# tas5753.net
KiCad netlist of a schematic drawn in EAGLE
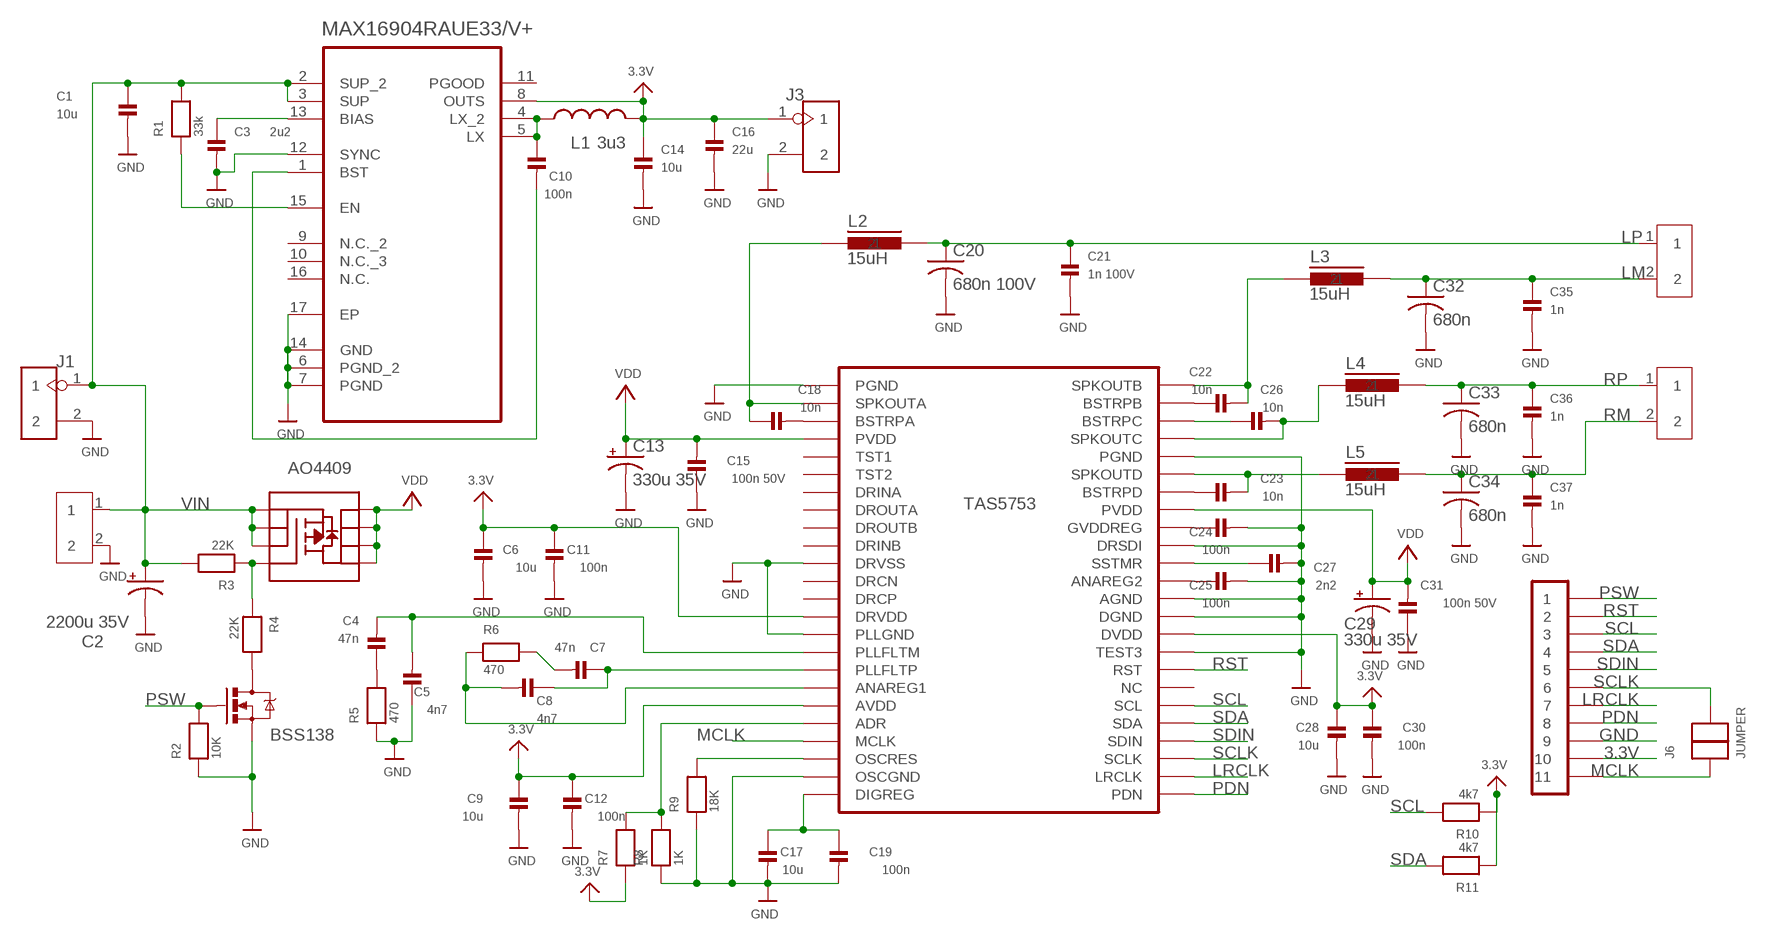
[diagram p0: schematic, sheet 1]

(export (version "E")
  (design (tool "Eeschema 10.0.6"))
  (components
    (comp (ref "C1")
      (value "10u")
      (footprint "eagle-import:0805")
      (libsource (lib "eagle-import") (part "CAP_CERAMIC0805"))
    )
    (comp (ref "C2")
      (value "2200u 35V")
      (footprint "eagle-import:CPOL-RADIAL-1000UF-25V")
      (libsource (lib "eagle-import") (part "CAP_POLPTH4"))
    )
    (comp (ref "C3")
      (value "2u2")
      (footprint "eagle-import:0805")
      (libsource (lib "eagle-import") (part "CAP_CERAMIC0805"))
    )
    (comp (ref "C4")
      (value "47n")
      (footprint "eagle-import:0603")
      (libsource (lib "eagle-import") (part "CAP_CERAMIC0603"))
    )
    (comp (ref "C5")
      (value "4n7")
      (footprint "eagle-import:0603")
      (libsource (lib "eagle-import") (part "CAP_CERAMIC0603"))
    )
    (comp (ref "C6")
      (value "10u")
      (footprint "eagle-import:0603")
      (libsource (lib "eagle-import") (part "CAP_CERAMIC0603"))
    )
    (comp (ref "C7")
      (value "47n")
      (footprint "eagle-import:0603")
      (libsource (lib "eagle-import") (part "CAP_CERAMIC0603"))
    )
    (comp (ref "C8")
      (value "4n7")
      (footprint "eagle-import:0603")
      (libsource (lib "eagle-import") (part "CAP_CERAMIC0603"))
    )
    (comp (ref "C9")
      (value "10u")
      (footprint "eagle-import:0603")
      (libsource (lib "eagle-import") (part "CAP_CERAMIC0603"))
    )
    (comp (ref "C10")
      (value "100n")
      (footprint "eagle-import:0603")
      (libsource (lib "eagle-import") (part "CAP_CERAMIC0603"))
    )
    (comp (ref "C11")
      (value "100n")
      (footprint "eagle-import:0603")
      (libsource (lib "eagle-import") (part "CAP_CERAMIC0603"))
    )
    (comp (ref "C12")
      (value "100n")
      (footprint "eagle-import:0603")
      (libsource (lib "eagle-import") (part "CAP_CERAMIC0603"))
    )
    (comp (ref "C13")
      (value "330u 35V")
      (footprint "eagle-import:PANASONIC_E")
      (libsource (lib "eagle-import") (part "CAP_POLE"))
    )
    (comp (ref "C14")
      (value "10u")
      (footprint "eagle-import:0805")
      (libsource (lib "eagle-import") (part "CAP_CERAMIC0805"))
    )
    (comp (ref "C15")
      (value "100n 50V")
      (footprint "eagle-import:0603")
      (libsource (lib "eagle-import") (part "CAP_CERAMIC0603"))
    )
    (comp (ref "C16")
      (value "22u")
      (footprint "eagle-import:1206")
      (libsource (lib "eagle-import") (part "CAP_CERAMIC1206"))
    )
    (comp (ref "C17")
      (value "10u")
      (footprint "eagle-import:0603")
      (libsource (lib "eagle-import") (part "CAP_CERAMIC0603"))
    )
    (comp (ref "C18")
      (value "10n")
      (footprint "eagle-import:0603")
      (libsource (lib "eagle-import") (part "CAP_CERAMIC0603"))
    )
    (comp (ref "C19")
      (value "100n")
      (footprint "eagle-import:0603")
      (libsource (lib "eagle-import") (part "CAP_CERAMIC0603"))
    )
    (comp (ref "C20")
      (value "680n 100V")
      (footprint "eagle-import:C050-045X075")
      (libsource (lib "eagle-import") (part "C-US050-045X075"))
    )
    (comp (ref "C21")
      (value "1n 100V")
      (footprint "eagle-import:1206")
      (libsource (lib "eagle-import") (part "CAP_CERAMIC1206"))
    )
    (comp (ref "C22")
      (value "10n")
      (footprint "eagle-import:0603")
      (libsource (lib "eagle-import") (part "CAP_CERAMIC0603"))
    )
    (comp (ref "C23")
      (value "10n")
      (footprint "eagle-import:0603")
      (libsource (lib "eagle-import") (part "CAP_CERAMIC0603"))
    )
    (comp (ref "C24")
      (value "100n")
      (footprint "eagle-import:0603")
      (libsource (lib "eagle-import") (part "CAP_CERAMIC0603"))
    )
    (comp (ref "C25")
      (value "100n")
      (footprint "eagle-import:0603")
      (libsource (lib "eagle-import") (part "CAP_CERAMIC0603"))
    )
    (comp (ref "C26")
      (value "10n")
      (footprint "eagle-import:0603")
      (libsource (lib "eagle-import") (part "CAP_CERAMIC0603"))
    )
    (comp (ref "C27")
      (value "2n2")
      (footprint "eagle-import:0603")
      (libsource (lib "eagle-import") (part "CAP_CERAMIC0603"))
    )
    (comp (ref "C28")
      (value "10u")
      (footprint "eagle-import:0603")
      (libsource (lib "eagle-import") (part "CAP_CERAMIC0603"))
    )
    (comp (ref "C29")
      (value "330u 35V")
      (footprint "eagle-import:PANASONIC_E")
      (libsource (lib "eagle-import") (part "CAP_POLE"))
    )
    (comp (ref "C30")
      (value "100n")
      (footprint "eagle-import:0603")
      (libsource (lib "eagle-import") (part "CAP_CERAMIC0603"))
    )
    (comp (ref "C31")
      (value "100n 50V")
      (footprint "eagle-import:0603")
      (libsource (lib "eagle-import") (part "CAP_CERAMIC0603"))
    )
    (comp (ref "C32")
      (value "680n")
      (footprint "eagle-import:C050-045X075")
      (libsource (lib "eagle-import") (part "C-US050-045X075"))
    )
    (comp (ref "C33")
      (value "680n")
      (footprint "eagle-import:C050-045X075")
      (libsource (lib "eagle-import") (part "C-US050-045X075"))
    )
    (comp (ref "C34")
      (value "680n")
      (footprint "eagle-import:C050-045X075")
      (libsource (lib "eagle-import") (part "C-US050-045X075"))
    )
    (comp (ref "C35")
      (value "1n")
      (footprint "eagle-import:1206")
      (libsource (lib "eagle-import") (part "CAP_CERAMIC1206"))
    )
    (comp (ref "C36")
      (value "1n")
      (footprint "eagle-import:1206")
      (libsource (lib "eagle-import") (part "CAP_CERAMIC1206"))
    )
    (comp (ref "C37")
      (value "1n")
      (footprint "eagle-import:1206")
      (libsource (lib "eagle-import") (part "CAP_CERAMIC1206"))
    )
    (comp (ref "IC1")
      (value "AO4409")
      (footprint "eagle-import:SO08")
      (libsource (lib "eagle-import") (part "MOSFET-PCHANNEL-SOIC8SOIC8"))
    )
    (comp (ref "J1")
      (value "HEADER-2P-2.0")
      (footprint "eagle-import:2P-2.0")
      (libsource (lib "eagle-import") (part "HEADER-2P-2.0"))
    )
    (comp (ref "J2")
      (value "SCREW-TERMINAL-2P'5.08'")
      (footprint "eagle-import:2P-5.08")
      (libsource (lib "eagle-import") (part "SCREW-TERMINAL-2P'5.08'"))
    )
    (comp (ref "J3")
      (value "HEADER-2P-2.0")
      (footprint "eagle-import:2P-2.0")
      (libsource (lib "eagle-import") (part "HEADER-2P-2.0"))
    )
    (comp (ref "J4")
      (value "SCREW-TERMINAL-2P'5.08'")
      (footprint "eagle-import:2P-5.08")
      (libsource (lib "eagle-import") (part "SCREW-TERMINAL-2P'5.08'"))
    )
    (comp (ref "J5")
      (value "SCREW-TERMINAL-2P'5.08'")
      (footprint "eagle-import:2P-5.08")
      (libsource (lib "eagle-import") (part "SCREW-TERMINAL-2P'5.08'"))
    )
    (comp (ref "J6")
      (value "JUMPER")
      (footprint "eagle-import:JUMPER")
      (libsource (lib "eagle-import") (part "JUMPER"))
    )
    (comp (ref "L1")
      (value "3u3")
      (footprint "eagle-import:CR54")
      (libsource (lib "eagle-import") (part "INDUCTORCR54"))
    )
    (comp (ref "L2")
      (value "15uH")
      (footprint "eagle-import:DR125")
      (libsource (lib "eagle-import") (part "DR125"))
    )
    (comp (ref "L3")
      (value "15uH")
      (footprint "eagle-import:DR125")
      (libsource (lib "eagle-import") (part "DR125"))
    )
    (comp (ref "L4")
      (value "15uH")
      (footprint "eagle-import:DR125")
      (libsource (lib "eagle-import") (part "DR125"))
    )
    (comp (ref "L5")
      (value "15uH")
      (footprint "eagle-import:DR125")
      (libsource (lib "eagle-import") (part "DR125"))
    )
    (comp (ref "P1")
      (value "CONN_1X11_SMT_254")
      (footprint "eagle-import:CONN_SMT_1X11_254")
      (libsource (lib "eagle-import") (part "CONN_1X11_SMT_254"))
    )
    (comp (ref "Q1")
      (value "BSS138")
      (footprint "eagle-import:SOT23")
      (libsource (lib "eagle-import") (part "MOSFET-NCHANNELBSS138"))
    )
    (comp (ref "R1")
      (value "33k")
      (footprint "eagle-import:0603")
      (libsource (lib "eagle-import") (part "RESISTOR0603"))
    )
    (comp (ref "R2")
      (value "10K")
      (footprint "eagle-import:0603")
      (libsource (lib "eagle-import") (part "RESISTOR0603"))
    )
    (comp (ref "R3")
      (value "22K")
      (footprint "eagle-import:0603")
      (libsource (lib "eagle-import") (part "RESISTOR0603"))
    )
    (comp (ref "R4")
      (value "22K")
      (footprint "eagle-import:0603")
      (libsource (lib "eagle-import") (part "RESISTOR0603"))
    )
    (comp (ref "R5")
      (value "470")
      (footprint "eagle-import:0603")
      (libsource (lib "eagle-import") (part "RESISTOR0603"))
    )
    (comp (ref "R6")
      (value "470")
      (footprint "eagle-import:0603")
      (libsource (lib "eagle-import") (part "RESISTOR0603"))
    )
    (comp (ref "R7")
      (value "1K")
      (footprint "eagle-import:0603")
      (libsource (lib "eagle-import") (part "RESISTOR0603"))
    )
    (comp (ref "R8")
      (value "1K")
      (footprint "eagle-import:0603")
      (libsource (lib "eagle-import") (part "RESISTOR0603"))
    )
    (comp (ref "R9")
      (value "18K")
      (footprint "eagle-import:0603")
      (libsource (lib "eagle-import") (part "RESISTOR0603"))
    )
    (comp (ref "R10")
      (value "4k7")
      (footprint "eagle-import:0603")
      (libsource (lib "eagle-import") (part "RESISTOR0603"))
    )
    (comp (ref "R11")
      (value "4k7")
      (footprint "eagle-import:0603")
      (libsource (lib "eagle-import") (part "RESISTOR0603"))
    )
    (comp (ref "U1")
      (value "MAX16904RAUE33/V+")
      (footprint "eagle-import:SOP65P638X110-17N")
      (libsource (lib "eagle-import") (part "MAX16904RAUE33/V+"))
    )
    (comp (ref "U2")
      (value "TAS5753")
      (footprint "eagle-import:HTSSOP_48")
      (libsource (lib "eagle-import") (part "TAS5753"))
    )
  )
  (nets
    (net (code "1") (name "/LM") (class "Default")
      (node (ref "C32") (pin "1") (pinfunction "1_1") (pintype "passive"))
      (node (ref "C35") (pin "1") (pinfunction "P$1_1") (pintype "passive"))
      (node (ref "J4") (pin "2") (pinfunction "2_2") (pintype "bidirectional"))
      (node (ref "L3") (pin "2") (pinfunction "2_2") (pintype "passive"))
    )
    (net (code "2") (name "/LP") (class "Default")
      (node (ref "C20") (pin "1") (pinfunction "1_1") (pintype "passive"))
      (node (ref "C21") (pin "1") (pinfunction "P$1_1") (pintype "passive"))
      (node (ref "J4") (pin "1") (pinfunction "1_1") (pintype "bidirectional"))
      (node (ref "L2") (pin "2") (pinfunction "2_2") (pintype "passive"))
    )
    (net (code "3") (name "/LRCLK") (class "Default")
      (node (ref "P1") (pin "P$7") (pinfunction "7_P$7") (pintype "bidirectional"))
      (node (ref "U2") (pin "P$26") (pinfunction "LRCLK_P$26") (pintype "bidirectional"))
    )
    (net (code "4") (name "/MCLK") (class "Default")
      (node (ref "J6") (pin "1") (pintype "bidirectional"))
      (node (ref "P1") (pin "P$11") (pinfunction "11_P$11") (pintype "bidirectional"))
      (node (ref "U2") (pin "P$21") (pinfunction "MCLK_P$21") (pintype "bidirectional"))
    )
    (net (code "5") (name "/PDN") (class "Default")
      (node (ref "P1") (pin "P$8") (pinfunction "8_P$8") (pintype "bidirectional"))
      (node (ref "U2") (pin "P$25") (pinfunction "PDN_P$25") (pintype "bidirectional"))
    )
    (net (code "6") (name "/PSW") (class "Default")
      (node (ref "P1") (pin "P$1") (pinfunction "1_P$1") (pintype "bidirectional"))
      (node (ref "Q1") (pin "1") (pinfunction "G_1") (pintype "passive"))
      (node (ref "R2") (pin "2") (pinfunction "2_2") (pintype "passive"))
    )
    (net (code "7") (name "/RM") (class "Default")
      (node (ref "C34") (pin "1") (pinfunction "1_1") (pintype "passive"))
      (node (ref "C37") (pin "1") (pinfunction "P$1_1") (pintype "passive"))
      (node (ref "J5") (pin "2") (pinfunction "2_2") (pintype "bidirectional"))
      (node (ref "L5") (pin "2") (pinfunction "2_2") (pintype "passive"))
    )
    (net (code "8") (name "/RP") (class "Default")
      (node (ref "C33") (pin "1") (pinfunction "1_1") (pintype "passive"))
      (node (ref "C36") (pin "1") (pinfunction "P$1_1") (pintype "passive"))
      (node (ref "J5") (pin "1") (pinfunction "1_1") (pintype "bidirectional"))
      (node (ref "L4") (pin "2") (pinfunction "2_2") (pintype "passive"))
    )
    (net (code "9") (name "/RST") (class "Default")
      (node (ref "P1") (pin "P$2") (pinfunction "2_P$2") (pintype "bidirectional"))
      (node (ref "U2") (pin "P$32") (pinfunction "RST_P$32") (pintype "bidirectional"))
    )
    (net (code "10") (name "/SCL") (class "Default")
      (node (ref "P1") (pin "P$3") (pinfunction "3_P$3") (pintype "bidirectional"))
      (node (ref "R10") (pin "2") (pinfunction "2_2") (pintype "passive"))
      (node (ref "U2") (pin "P$30") (pinfunction "SCL_P$30") (pintype "bidirectional"))
    )
    (net (code "11") (name "/SCLK") (class "Default")
      (node (ref "J6") (pin "2") (pintype "bidirectional"))
      (node (ref "P1") (pin "P$6") (pinfunction "6_P$6") (pintype "bidirectional"))
      (node (ref "U2") (pin "P$27") (pinfunction "SCLK_P$27") (pintype "bidirectional"))
    )
    (net (code "12") (name "/SDA") (class "Default")
      (node (ref "P1") (pin "P$4") (pinfunction "4_P$4") (pintype "bidirectional"))
      (node (ref "R11") (pin "2") (pinfunction "2_2") (pintype "passive"))
      (node (ref "U2") (pin "P$29") (pinfunction "SDA_P$29") (pintype "bidirectional"))
    )
    (net (code "13") (name "/SDIN") (class "Default")
      (node (ref "P1") (pin "P$5") (pinfunction "5_P$5") (pintype "bidirectional"))
      (node (ref "U2") (pin "P$28") (pinfunction "SDIN_P$28") (pintype "bidirectional"))
    )
    (net (code "14") (name "/VIN") (class "Default")
      (node (ref "C1") (pin "1") (pinfunction "P$1_1") (pintype "passive"))
      (node (ref "C2") (pin "1") (pinfunction "+_1") (pintype "passive"))
      (node (ref "IC1") (pin "1") (pinfunction "S_1") (pintype "bidirectional"))
      (node (ref "IC1") (pin "2") (pinfunction "S_2") (pintype "bidirectional"))
      (node (ref "IC1") (pin "3") (pinfunction "S_3") (pintype "bidirectional"))
      (node (ref "J1") (pin "1") (pinfunction "1_1") (pintype "bidirectional"))
      (node (ref "J2") (pin "1") (pinfunction "1_1") (pintype "bidirectional"))
      (node (ref "R1") (pin "2") (pinfunction "2_2") (pintype "passive"))
      (node (ref "R3") (pin "2") (pinfunction "2_2") (pintype "passive"))
      (node (ref "U1") (pin "2") (pinfunction "SUP_2_2") (pintype "power_in"))
      (node (ref "U1") (pin "3") (pinfunction "SUP_3") (pintype "power_in"))
    )
    (net (code "15") (name "3.3V") (class "Default")
      (node (ref "C11") (pin "1") (pinfunction "P$1_1") (pintype "passive"))
      (node (ref "C12") (pin "1") (pinfunction "P$1_1") (pintype "passive"))
      (node (ref "C14") (pin "1") (pinfunction "P$1_1") (pintype "passive"))
      (node (ref "C16") (pin "1") (pinfunction "P$1_1") (pintype "passive"))
      (node (ref "C28") (pin "1") (pinfunction "P$1_1") (pintype "passive"))
      (node (ref "C30") (pin "1") (pinfunction "P$1_1") (pintype "passive"))
      (node (ref "C6") (pin "1") (pinfunction "P$1_1") (pintype "passive"))
      (node (ref "C9") (pin "1") (pinfunction "P$1_1") (pintype "passive"))
      (node (ref "J3") (pin "1") (pinfunction "1_1") (pintype "bidirectional"))
      (node (ref "L1") (pin "P$2") (pinfunction "2_P$2") (pintype "passive"))
      (node (ref "P1") (pin "P$10") (pinfunction "10_P$10") (pintype "bidirectional"))
      (node (ref "R10") (pin "1") (pinfunction "1_1") (pintype "passive"))
      (node (ref "R11") (pin "1") (pinfunction "1_1") (pintype "passive"))
      (node (ref "R7") (pin "1") (pinfunction "1_1") (pintype "passive"))
      (node (ref "U1") (pin "8") (pinfunction "OUTS_8") (pintype "output"))
      (node (ref "U2") (pin "P$14") (pinfunction "DRVDD_P$14") (pintype "bidirectional"))
      (node (ref "U2") (pin "P$19") (pinfunction "AVDD_P$19") (pintype "bidirectional"))
      (node (ref "U2") (pin "P$34") (pinfunction "DVDD_P$34") (pintype "bidirectional"))
    )
    (net (code "16") (name "GND") (class "Default")
      (node (ref "C1") (pin "2") (pinfunction "P$2_2") (pintype "passive"))
      (node (ref "C11") (pin "2") (pinfunction "P$2_2") (pintype "passive"))
      (node (ref "C12") (pin "2") (pinfunction "P$2_2") (pintype "passive"))
      (node (ref "C13") (pin "-") (pinfunction "-_-") (pintype "passive"))
      (node (ref "C14") (pin "2") (pinfunction "P$2_2") (pintype "passive"))
      (node (ref "C15") (pin "1") (pinfunction "P$1_1") (pintype "passive"))
      (node (ref "C16") (pin "2") (pinfunction "P$2_2") (pintype "passive"))
      (node (ref "C17") (pin "2") (pinfunction "P$2_2") (pintype "passive"))
      (node (ref "C19") (pin "2") (pinfunction "P$2_2") (pintype "passive"))
      (node (ref "C2") (pin "2") (pinfunction "-_2") (pintype "passive"))
      (node (ref "C20") (pin "2") (pinfunction "2_2") (pintype "passive"))
      (node (ref "C21") (pin "2") (pinfunction "P$2_2") (pintype "passive"))
      (node (ref "C24") (pin "2") (pinfunction "P$2_2") (pintype "passive"))
      (node (ref "C25") (pin "2") (pinfunction "P$2_2") (pintype "passive"))
      (node (ref "C27") (pin "2") (pinfunction "P$2_2") (pintype "passive"))
      (node (ref "C28") (pin "2") (pinfunction "P$2_2") (pintype "passive"))
      (node (ref "C29") (pin "-") (pinfunction "-_-") (pintype "passive"))
      (node (ref "C3") (pin "2") (pinfunction "P$2_2") (pintype "passive"))
      (node (ref "C30") (pin "2") (pinfunction "P$2_2") (pintype "passive"))
      (node (ref "C31") (pin "1") (pinfunction "P$1_1") (pintype "passive"))
      (node (ref "C32") (pin "2") (pinfunction "2_2") (pintype "passive"))
      (node (ref "C33") (pin "2") (pinfunction "2_2") (pintype "passive"))
      (node (ref "C34") (pin "2") (pinfunction "2_2") (pintype "passive"))
      (node (ref "C35") (pin "2") (pinfunction "P$2_2") (pintype "passive"))
      (node (ref "C36") (pin "2") (pinfunction "P$2_2") (pintype "passive"))
      (node (ref "C37") (pin "2") (pinfunction "P$2_2") (pintype "passive"))
      (node (ref "C5") (pin "1") (pinfunction "P$1_1") (pintype "passive"))
      (node (ref "C6") (pin "2") (pinfunction "P$2_2") (pintype "passive"))
      (node (ref "C9") (pin "2") (pinfunction "P$2_2") (pintype "passive"))
      (node (ref "J1") (pin "2") (pinfunction "2_2") (pintype "bidirectional"))
      (node (ref "J2") (pin "2") (pinfunction "2_2") (pintype "bidirectional"))
      (node (ref "J3") (pin "2") (pinfunction "2_2") (pintype "bidirectional"))
      (node (ref "P1") (pin "P$9") (pinfunction "9_P$9") (pintype "bidirectional"))
      (node (ref "Q1") (pin "2") (pinfunction "S_2") (pintype "passive"))
      (node (ref "R2") (pin "1") (pinfunction "1_1") (pintype "passive"))
      (node (ref "R5") (pin "1") (pinfunction "1_1") (pintype "passive"))
      (node (ref "R8") (pin "1") (pinfunction "1_1") (pintype "passive"))
      (node (ref "R9") (pin "1") (pinfunction "1_1") (pintype "passive"))
      (node (ref "U1") (pin "12") (pinfunction "SYNC_12") (pintype "input"))
      (node (ref "U1") (pin "14") (pinfunction "GND_14") (pintype "passive"))
      (node (ref "U1") (pin "17") (pinfunction "EP_17") (pintype "passive"))
      (node (ref "U1") (pin "6") (pinfunction "PGND_2_6") (pintype "passive"))
      (node (ref "U1") (pin "7") (pinfunction "PGND_7") (pintype "passive"))
      (node (ref "U2") (pin "P$1") (pinfunction "PGND_P$1") (pintype "bidirectional"))
      (node (ref "U2") (pin "P$11") (pinfunction "DRVSS_P$11") (pintype "bidirectional"))
      (node (ref "U2") (pin "P$15") (pinfunction "PLLGND_P$15") (pintype "bidirectional"))
      (node (ref "U2") (pin "P$23") (pinfunction "OSCGND_P$23") (pintype "bidirectional"))
      (node (ref "U2") (pin "P$33") (pinfunction "TEST3_P$33") (pintype "bidirectional"))
      (node (ref "U2") (pin "P$35") (pinfunction "DGND_P$35") (pintype "bidirectional"))
      (node (ref "U2") (pin "P$36") (pinfunction "AGND_P$36") (pintype "bidirectional"))
      (node (ref "U2") (pin "P$39") (pinfunction "DRSDI_P$39") (pintype "bidirectional"))
      (node (ref "U2") (pin "P$44") (pinfunction "PGND_P$44") (pintype "bidirectional"))
      (node (ref "U2") (pin "P$49") (pinfunction "PGND_P$49") (pintype "bidirectional"))
    )
    (net (code "17") (name "Net-(C3-P$1)") (class "Default")
      (node (ref "C3") (pin "1") (pinfunction "P$1_1") (pintype "passive"))
      (node (ref "U1") (pin "13") (pinfunction "BIAS_13") (pintype "power_in"))
    )
    (net (code "18") (name "Net-(C4-P$1)") (class "Default")
      (node (ref "C4") (pin "1") (pinfunction "P$1_1") (pintype "passive"))
      (node (ref "R5") (pin "2") (pinfunction "2_2") (pintype "passive"))
    )
    (net (code "19") (name "Net-(C4-P$2)") (class "Default")
      (node (ref "C4") (pin "2") (pinfunction "P$2_2") (pintype "passive"))
      (node (ref "C5") (pin "2") (pinfunction "P$2_2") (pintype "passive"))
      (node (ref "U2") (pin "P$16") (pinfunction "PLLFLTM_P$16") (pintype "bidirectional"))
    )
    (net (code "20") (name "Net-(C7-P$1)") (class "Default")
      (node (ref "C7") (pin "1") (pinfunction "P$1_1") (pintype "passive"))
      (node (ref "C8") (pin "1") (pinfunction "P$1_1") (pintype "passive"))
      (node (ref "U2") (pin "P$17") (pinfunction "PLLFLTP_P$17") (pintype "bidirectional"))
    )
    (net (code "21") (name "Net-(C7-P$2)") (class "Default")
      (node (ref "C7") (pin "2") (pinfunction "P$2_2") (pintype "passive"))
      (node (ref "R6") (pin "2") (pinfunction "2_2") (pintype "passive"))
    )
    (net (code "22") (name "Net-(C8-P$2)") (class "Default")
      (node (ref "C8") (pin "2") (pinfunction "P$2_2") (pintype "passive"))
      (node (ref "R6") (pin "1") (pinfunction "1_1") (pintype "passive"))
      (node (ref "U2") (pin "P$18") (pinfunction "ANAREG1_P$18") (pintype "bidirectional"))
    )
    (net (code "23") (name "Net-(C10-P$1)") (class "Default")
      (node (ref "C10") (pin "1") (pinfunction "P$1_1") (pintype "passive"))
      (node (ref "L1") (pin "P$1") (pinfunction "1_P$1") (pintype "passive"))
      (node (ref "U1") (pin "4") (pinfunction "LX_2_4") (pintype "output"))
      (node (ref "U1") (pin "5") (pinfunction "LX_5") (pintype "output"))
    )
    (net (code "24") (name "Net-(C10-P$2)") (class "Default")
      (node (ref "C10") (pin "2") (pinfunction "P$2_2") (pintype "passive"))
      (node (ref "U1") (pin "1") (pinfunction "BST_1") (pintype "passive"))
    )
    (net (code "25") (name "Net-(C17-P$1)") (class "Default")
      (node (ref "C17") (pin "1") (pinfunction "P$1_1") (pintype "passive"))
      (node (ref "C19") (pin "1") (pinfunction "P$1_1") (pintype "passive"))
      (node (ref "U2") (pin "P$24") (pinfunction "DIGREG_P$24") (pintype "bidirectional"))
    )
    (net (code "26") (name "Net-(C18-P$1)") (class "Default")
      (node (ref "C18") (pin "1") (pinfunction "P$1_1") (pintype "passive"))
      (node (ref "L2") (pin "1") (pinfunction "1_1") (pintype "passive"))
      (node (ref "U2") (pin "P$2") (pinfunction "SPKOUTA_P$2") (pintype "bidirectional"))
    )
    (net (code "27") (name "Net-(C18-P$2)") (class "Default")
      (node (ref "C18") (pin "2") (pinfunction "P$2_2") (pintype "passive"))
      (node (ref "U2") (pin "P$3") (pinfunction "BSTRPA_P$3") (pintype "bidirectional"))
    )
    (net (code "28") (name "Net-(C22-P$1)") (class "Default")
      (node (ref "C22") (pin "1") (pinfunction "P$1_1") (pintype "passive"))
      (node (ref "U2") (pin "P$47") (pinfunction "BSTRPB_P$47") (pintype "bidirectional"))
    )
    (net (code "29") (name "Net-(C22-P$2)") (class "Default")
      (node (ref "C22") (pin "2") (pinfunction "P$2_2") (pintype "passive"))
      (node (ref "L3") (pin "1") (pinfunction "1_1") (pintype "passive"))
      (node (ref "U2") (pin "P$48") (pinfunction "SPKOUTB_P$48") (pintype "bidirectional"))
    )
    (net (code "30") (name "Net-(C23-P$1)") (class "Default")
      (node (ref "C23") (pin "1") (pinfunction "P$1_1") (pintype "passive"))
      (node (ref "U2") (pin "P$42") (pinfunction "BSTRPD_P$42") (pintype "bidirectional"))
    )
    (net (code "31") (name "Net-(C23-P$2)") (class "Default")
      (node (ref "C23") (pin "2") (pinfunction "P$2_2") (pintype "passive"))
      (node (ref "L5") (pin "1") (pinfunction "1_1") (pintype "passive"))
      (node (ref "U2") (pin "P$43") (pinfunction "SPKOUTD_P$43") (pintype "bidirectional"))
    )
    (net (code "32") (name "Net-(C24-P$1)") (class "Default")
      (node (ref "C24") (pin "1") (pinfunction "P$1_1") (pintype "passive"))
      (node (ref "U2") (pin "P$40") (pinfunction "GVDDREG_P$40") (pintype "bidirectional"))
    )
    (net (code "33") (name "Net-(C25-P$1)") (class "Default")
      (node (ref "C25") (pin "1") (pinfunction "P$1_1") (pintype "passive"))
      (node (ref "U2") (pin "P$37") (pinfunction "ANAREG2_P$37") (pintype "bidirectional"))
    )
    (net (code "34") (name "Net-(C26-P$1)") (class "Default")
      (node (ref "C26") (pin "1") (pinfunction "P$1_1") (pintype "passive"))
      (node (ref "U2") (pin "P$46") (pinfunction "BSTRPC_P$46") (pintype "bidirectional"))
    )
    (net (code "35") (name "Net-(C26-P$2)") (class "Default")
      (node (ref "C26") (pin "2") (pinfunction "P$2_2") (pintype "passive"))
      (node (ref "L4") (pin "1") (pinfunction "1_1") (pintype "passive"))
      (node (ref "U2") (pin "P$45") (pinfunction "SPKOUTC_P$45") (pintype "bidirectional"))
    )
    (net (code "36") (name "Net-(C27-P$1)") (class "Default")
      (node (ref "C27") (pin "1") (pinfunction "P$1_1") (pintype "passive"))
      (node (ref "U2") (pin "P$38") (pinfunction "SSTMR_P$38") (pintype "bidirectional"))
    )
    (net (code "37") (name "Net-(IC1-G)") (class "Default")
      (node (ref "IC1") (pin "4") (pinfunction "G_4") (pintype "bidirectional"))
      (node (ref "R3") (pin "1") (pinfunction "1_1") (pintype "passive"))
      (node (ref "R4") (pin "1") (pinfunction "1_1") (pintype "passive"))
    )
    (net (code "38") (name "Net-(Q1-D)") (class "Default")
      (node (ref "Q1") (pin "3") (pinfunction "D_3") (pintype "passive"))
      (node (ref "R4") (pin "2") (pinfunction "2_2") (pintype "passive"))
    )
    (net (code "39") (name "Net-(U1-EN)") (class "Default")
      (node (ref "R1") (pin "1") (pinfunction "1_1") (pintype "passive"))
      (node (ref "U1") (pin "15") (pinfunction "EN_15") (pintype "input"))
    )
    (net (code "40") (name "Net-(U2-ADR)") (class "Default")
      (node (ref "R7") (pin "2") (pinfunction "2_2") (pintype "passive"))
      (node (ref "R8") (pin "2") (pinfunction "2_2") (pintype "passive"))
      (node (ref "U2") (pin "P$20") (pinfunction "ADR_P$20") (pintype "bidirectional"))
    )
    (net (code "41") (name "Net-(U2-OSCRES)") (class "Default")
      (node (ref "R9") (pin "2") (pinfunction "2_2") (pintype "passive"))
      (node (ref "U2") (pin "P$22") (pinfunction "OSCRES_P$22") (pintype "bidirectional"))
    )
    (net (code "42") (name "VDD") (class "Default")
      (node (ref "C13") (pin "+") (pinfunction "+_+") (pintype "passive"))
      (node (ref "C15") (pin "2") (pinfunction "P$2_2") (pintype "passive"))
      (node (ref "C29") (pin "+") (pinfunction "+_+") (pintype "passive"))
      (node (ref "C31") (pin "2") (pinfunction "P$2_2") (pintype "passive"))
      (node (ref "IC1") (pin "5") (pinfunction "D_5") (pintype "bidirectional"))
      (node (ref "IC1") (pin "6") (pinfunction "D_6") (pintype "bidirectional"))
      (node (ref "IC1") (pin "7") (pinfunction "D_7") (pintype "bidirectional"))
      (node (ref "IC1") (pin "8") (pinfunction "D_8") (pintype "bidirectional"))
      (node (ref "U2") (pin "P$4") (pinfunction "PVDD_P$4") (pintype "bidirectional"))
      (node (ref "U2") (pin "P$41") (pinfunction "PVDD_P$41") (pintype "bidirectional"))
    )
    (net (code "43") (name "unconnected-(U1-N.C.-Pad16)") (class "Default")
      (node (ref "U1") (pin "16") (pinfunction "N.C._16") (pintype "no_connect"))
    )
    (net (code "44") (name "unconnected-(U1-N.C._2-Pad9)") (class "Default")
      (node (ref "U1") (pin "9") (pinfunction "N.C._2_9") (pintype "no_connect"))
    )
    (net (code "45") (name "unconnected-(U1-N.C._3-Pad10)") (class "Default")
      (node (ref "U1") (pin "10") (pinfunction "N.C._3_10") (pintype "no_connect"))
    )
    (net (code "46") (name "unconnected-(U1-PGOOD-Pad11)") (class "Default")
      (node (ref "U1") (pin "11") (pinfunction "PGOOD_11") (pintype "output"))
    )
    (net (code "47") (name "unconnected-(U2-DRCN-PadP$12)") (class "Default")
      (node (ref "U2") (pin "P$12") (pinfunction "DRCN_P$12") (pintype "bidirectional"))
    )
    (net (code "48") (name "unconnected-(U2-DRCP-PadP$13)") (class "Default")
      (node (ref "U2") (pin "P$13") (pinfunction "DRCP_P$13") (pintype "bidirectional"))
    )
    (net (code "49") (name "unconnected-(U2-DRINA-PadP$7)") (class "Default")
      (node (ref "U2") (pin "P$7") (pinfunction "DRINA_P$7") (pintype "bidirectional"))
    )
    (net (code "50") (name "unconnected-(U2-DRINB-PadP$10)") (class "Default")
      (node (ref "U2") (pin "P$10") (pinfunction "DRINB_P$10") (pintype "bidirectional"))
    )
    (net (code "51") (name "unconnected-(U2-DROUTA-PadP$8)") (class "Default")
      (node (ref "U2") (pin "P$8") (pinfunction "DROUTA_P$8") (pintype "bidirectional"))
    )
    (net (code "52") (name "unconnected-(U2-DROUTB-PadP$9)") (class "Default")
      (node (ref "U2") (pin "P$9") (pinfunction "DROUTB_P$9") (pintype "bidirectional"))
    )
    (net (code "53") (name "unconnected-(U2-NC-PadP$31)") (class "Default")
      (node (ref "U2") (pin "P$31") (pinfunction "NC_P$31") (pintype "bidirectional"))
    )
    (net (code "54") (name "unconnected-(U2-TST1-PadP$5)") (class "Default")
      (node (ref "U2") (pin "P$5") (pinfunction "TST1_P$5") (pintype "bidirectional"))
    )
    (net (code "55") (name "unconnected-(U2-TST2-PadP$6)") (class "Default")
      (node (ref "U2") (pin "P$6") (pinfunction "TST2_P$6") (pintype "bidirectional"))
    )
  )
)
